# Sheet2.net
KiCad netlist of a schematic drawn in Altium Designer
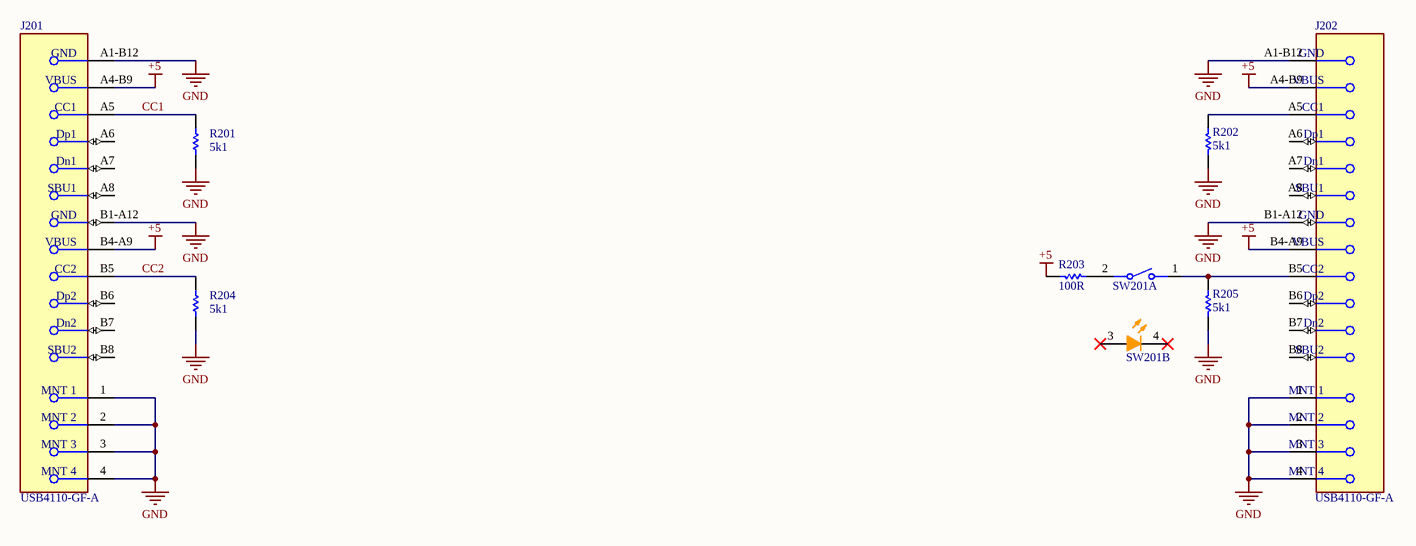
[diagram p0: Sheet2.SchDoc]

(export (version "E")
  (design (tool "Eeschema 10.0.6"))
  (components
    (comp (ref "J201")
      (value "USB4110-GF-A")
      (footprint "FP-USB4110-GF-A-MFG")
      (description "CONN USB 2.0 TYPE-C R/A SMT")
      (fields
        (field (name "OCTOPART") "https://octopart.com/usb4110-gf-a-gct-103941985")
        (field (name "MANUFACTURER") "GCT")
      )
      (libsource (lib "") (part "e23f2b38bb3c3f98e683ebab9ede730_1"))
    )
    (comp (ref "J202")
      (value "USB4110-GF-A")
      (footprint "FP-USB4110-GF-A-MFG")
      (description "CONN USB 2.0 TYPE-C R/A SMT")
      (fields
        (field (name "OCTOPART") "https://octopart.com/usb4110-gf-a-gct-103941985")
        (field (name "MANUFACTURER") "GCT")
      )
      (libsource (lib "Altium Content Vault") (part "e23f2b38bb3c3f98e683ebab9ede730"))
    )
    (comp (ref "R201")
      (value "5k1")
      (footprint "RESC1608X06N")
      (description "Resistor")
      (libsource (lib "Schlib1") (part "R0603"))
    )
    (comp (ref "R202")
      (value "5k1")
      (footprint "RESC1608X06N")
      (description "Resistor")
      (libsource (lib "Schlib1") (part "R0603"))
    )
    (comp (ref "R203")
      (value "100R")
      (footprint "RESC1608X06N")
      (description "Resistor")
      (libsource (lib "Schlib1") (part "R0603"))
    )
    (comp (ref "R204")
      (value "5k1")
      (footprint "RESC1608X06N")
      (description "Resistor")
      (libsource (lib "Schlib1") (part "R0603"))
    )
    (comp (ref "R205")
      (value "5k1")
      (footprint "RESC1608X06N")
      (description "Resistor")
      (libsource (lib "Schlib1") (part "R0603"))
    )
    (comp (ref "SW201")
      (value "Switch")
      (footprint "CHRY-MX")
      (description "Keylock Switch, 12 V, -10 to 70 degC, 2-Pin THD, RoHS, Bulk")
      (fields (field (name "MANUFACTURER") "Cherry") (field (name "PART NO") "MX1A11NW"))
      (libsource (lib "Schlib1") (part "Cherry MX"))
    )
  )
  (nets
    (net (code "1") (name "+5") (class "Default")
      (node (ref "J201") (pin "A4-B9") (pinfunction "VBUS_A4-B9") (pintype "power_in"))
      (node (ref "J201") (pin "B4-A9") (pinfunction "VBUS_B4-A9") (pintype "power_in"))
      (node (ref "J202") (pin "A4-B9") (pinfunction "VBUS_A4-B9") (pintype "power_in"))
      (node (ref "J202") (pin "B4-A9") (pinfunction "VBUS_B4-A9") (pintype "power_in"))
      (node (ref "R203") (pin "2") (pintype "passive"))
    )
    (net (code "2") (name "/CC1") (class "Default")
      (node (ref "J201") (pin "A5") (pinfunction "CC1_A5") (pintype "power_in"))
      (node (ref "R201") (pin "2") (pintype "passive"))
    )
    (net (code "3") (name "/CC2") (class "Default")
      (node (ref "J201") (pin "B5") (pinfunction "CC2_B5") (pintype "power_in"))
      (node (ref "R204") (pin "2") (pintype "passive"))
    )
    (net (code "4") (name "GND") (class "Default")
      (node (ref "J201") (pin "1") (pinfunction "MNT_1_1") (pintype "passive"))
      (node (ref "J201") (pin "2") (pinfunction "MNT_2_2") (pintype "passive"))
      (node (ref "J201") (pin "3") (pinfunction "MNT_3_3") (pintype "passive"))
      (node (ref "J201") (pin "4") (pinfunction "MNT_4_4") (pintype "passive"))
      (node (ref "J201") (pin "A1-B12") (pinfunction "GND_A1-B12") (pintype "passive"))
      (node (ref "J201") (pin "B1-A12") (pinfunction "GND_B1-A12") (pintype "bidirectional"))
      (node (ref "J202") (pin "1") (pinfunction "MNT_1_1") (pintype "passive"))
      (node (ref "J202") (pin "2") (pinfunction "MNT_2_2") (pintype "passive"))
      (node (ref "J202") (pin "3") (pinfunction "MNT_3_3") (pintype "passive"))
      (node (ref "J202") (pin "4") (pinfunction "MNT_4_4") (pintype "passive"))
      (node (ref "J202") (pin "A1-B12") (pinfunction "GND_A1-B12") (pintype "passive"))
      (node (ref "J202") (pin "B1-A12") (pinfunction "GND_B1-A12") (pintype "bidirectional"))
      (node (ref "R201") (pin "1") (pintype "passive"))
      (node (ref "R202") (pin "1") (pintype "passive"))
      (node (ref "R204") (pin "1") (pintype "passive"))
      (node (ref "R205") (pin "1") (pintype "passive"))
    )
    (net (code "5") (name "Net-(J202-CC1)") (class "Default")
      (node (ref "J202") (pin "A5") (pinfunction "CC1_A5") (pintype "power_in"))
      (node (ref "R202") (pin "2") (pintype "passive"))
    )
    (net (code "6") (name "Net-(J202-CC2)") (class "Default")
      (node (ref "J202") (pin "B5") (pinfunction "CC2_B5") (pintype "power_in"))
      (node (ref "R205") (pin "2") (pintype "passive"))
      (node (ref "SW201") (pin "1") (pinfunction "1_1") (pintype "passive"))
    )
    (net (code "7") (name "Net-(R203-Pad1)") (class "Default")
      (node (ref "R203") (pin "1") (pintype "passive"))
      (node (ref "SW201") (pin "2") (pinfunction "2_2") (pintype "passive"))
    )
    (net (code "8") (name "unconnected-(J201-Dn1-PadA7)") (class "Default")
      (node (ref "J201") (pin "A7") (pinfunction "Dn1_A7") (pintype "bidirectional"))
    )
    (net (code "9") (name "unconnected-(J201-Dn2-PadB7)") (class "Default")
      (node (ref "J201") (pin "B7") (pinfunction "Dn2_B7") (pintype "bidirectional"))
    )
    (net (code "10") (name "unconnected-(J201-Dp1-PadA6)") (class "Default")
      (node (ref "J201") (pin "A6") (pinfunction "Dp1_A6") (pintype "bidirectional"))
    )
    (net (code "11") (name "unconnected-(J201-Dp2-PadB6)") (class "Default")
      (node (ref "J201") (pin "B6") (pinfunction "Dp2_B6") (pintype "bidirectional"))
    )
    (net (code "12") (name "unconnected-(J201-SBU1-PadA8)") (class "Default")
      (node (ref "J201") (pin "A8") (pinfunction "SBU1_A8") (pintype "bidirectional"))
    )
    (net (code "13") (name "unconnected-(J201-SBU2-PadB8)") (class "Default")
      (node (ref "J201") (pin "B8") (pinfunction "SBU2_B8") (pintype "bidirectional"))
    )
    (net (code "14") (name "unconnected-(J202-Dn1-PadA7)") (class "Default")
      (node (ref "J202") (pin "A7") (pinfunction "Dn1_A7") (pintype "bidirectional"))
    )
    (net (code "15") (name "unconnected-(J202-Dn2-PadB7)") (class "Default")
      (node (ref "J202") (pin "B7") (pinfunction "Dn2_B7") (pintype "bidirectional"))
    )
    (net (code "16") (name "unconnected-(J202-Dp1-PadA6)") (class "Default")
      (node (ref "J202") (pin "A6") (pinfunction "Dp1_A6") (pintype "bidirectional"))
    )
    (net (code "17") (name "unconnected-(J202-Dp2-PadB6)") (class "Default")
      (node (ref "J202") (pin "B6") (pinfunction "Dp2_B6") (pintype "bidirectional"))
    )
    (net (code "18") (name "unconnected-(J202-SBU1-PadA8)") (class "Default")
      (node (ref "J202") (pin "A8") (pinfunction "SBU1_A8") (pintype "bidirectional"))
    )
    (net (code "19") (name "unconnected-(J202-SBU2-PadB8)") (class "Default")
      (node (ref "J202") (pin "B8") (pinfunction "SBU2_B8") (pintype "bidirectional"))
    )
    (net (code "20") (name "unconnected-(SW201B-A-Pad3)") (class "Default")
      (node (ref "SW201") (pin "3") (pinfunction "A_3") (pintype "passive+no_connect"))
    )
    (net (code "21") (name "unconnected-(SW201B-K-Pad4)") (class "Default")
      (node (ref "SW201") (pin "4") (pinfunction "K_4") (pintype "passive+no_connect"))
    )
  )
)
